# Polos_y_Ceros.net
KiCad netlist of a schematic drawn in Altium Designer
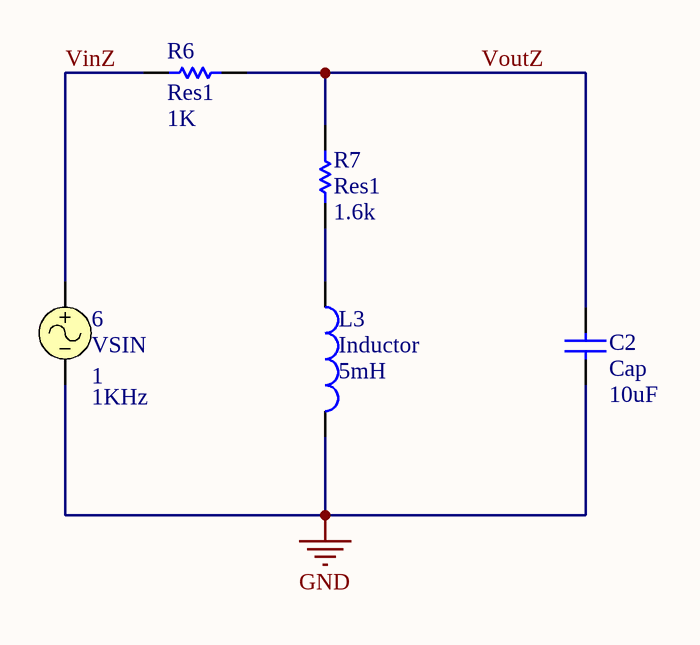
[diagram p0: Polos y Ceros.SchDoc]

(export (version "E")
  (design (tool "Eeschema 10.0.6"))
  (components
    (comp (ref "6")
      (value "VSIN")
      (description "Sinusoidal Voltage Source")
      (fields
        (field (name "AMPLITUDE") "1")
        (field (name "FREQUENCY") "1KHz")
        (field (name "PUBLISHER") "Altium Limited")
      )
      (libsource (lib "Simulation Sources") (part "VSIN"))
    )
    (comp (ref "C2")
      (value "Cap")
      (footprint "RAD-0.3")
      (description "Capacitor")
      (fields (field (name "ALTIUM_VALUE") "10uF") (field (name "PUBLISHER") "Altium Limited"))
      (libsource (lib "Miscellaneous Devices") (part "Cap"))
    )
    (comp (ref "L3")
      (value "Inductor")
      (footprint "0402-A")
      (fields (field (name "ALTIUM_VALUE") "5mH") (field (name "PUBLISHER") "Altium Limited"))
      (libsource (lib "Miscellaneous Devices") (part "Inductor"))
    )
    (comp (ref "R6")
      (value "Res1")
      (footprint "AXIAL-0.3")
      (description "Resistor")
      (fields (field (name "ALTIUM_VALUE") "1K") (field (name "PUBLISHER") "Altium Limited"))
      (libsource (lib "Miscellaneous Devices") (part "Res1"))
    )
    (comp (ref "R7")
      (value "Res1")
      (footprint "AXIAL-0.3")
      (description "Resistor")
      (fields (field (name "ALTIUM_VALUE") "1.6k") (field (name "PUBLISHER") "Altium Limited"))
      (libsource (lib "Miscellaneous Devices") (part "Res1"))
    )
  )
  (nets
    (net (code "1") (name "/VinZ") (class "Default")
      (node (ref "6") (pin "1") (pinfunction "1_1") (pintype "passive"))
      (node (ref "R6") (pin "1") (pinfunction "1_1") (pintype "passive"))
    )
    (net (code "2") (name "/VoutZ") (class "Default")
      (node (ref "C2") (pin "2") (pinfunction "2_2") (pintype "passive"))
      (node (ref "R6") (pin "2") (pinfunction "2_2") (pintype "passive"))
      (node (ref "R7") (pin "1") (pinfunction "1_1") (pintype "passive"))
    )
    (net (code "3") (name "GND") (class "Default")
      (node (ref "6") (pin "2") (pinfunction "2_2") (pintype "passive"))
      (node (ref "C2") (pin "1") (pinfunction "1_1") (pintype "passive"))
      (node (ref "L3") (pin "2") (pinfunction "2_2") (pintype "passive"))
    )
    (net (code "4") (name "Net-(L3-Pad1)") (class "Default")
      (node (ref "L3") (pin "1") (pinfunction "1_1") (pintype "passive"))
      (node (ref "R7") (pin "2") (pinfunction "2_2") (pintype "passive"))
    )
  )
)
